# first.net
KiCad netlist of a schematic drawn in EAGLE
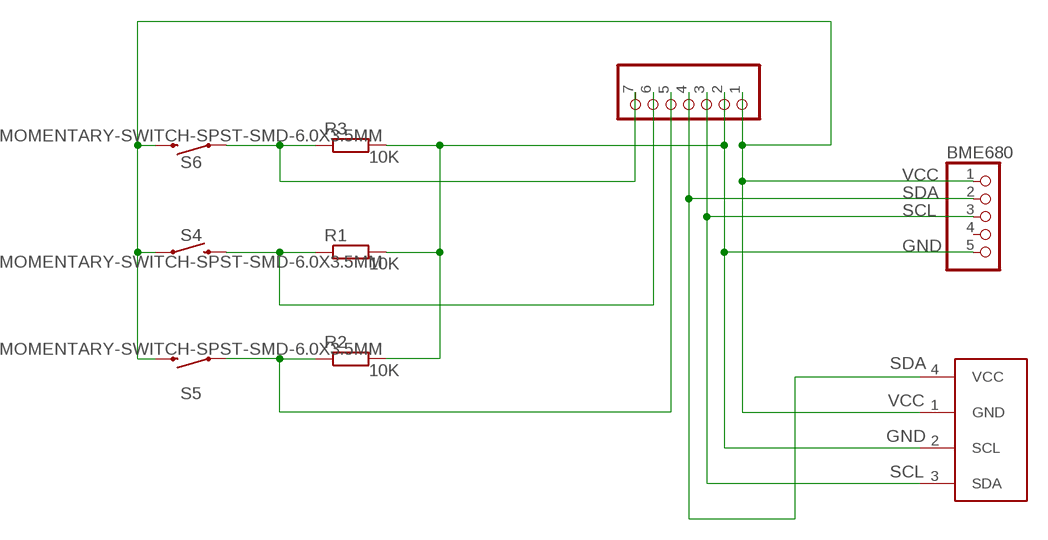
[diagram p0: schematic, sheet 1]

(export (version "E")
  (design (tool "Eeschema 10.0.6"))
  (components
    (comp (ref "BME680")
      (value "PINHD-1X5")
      (footprint "eagle-import:1X05")
      (libsource (lib "eagle-import") (part "PINHD-1X5"))
    )
    (comp (ref "R1")
      (value "R-EU_M1206")
      (footprint "eagle-import:M1206")
      (fields (field (name "SPICEPREFIX") "R") (field (name "SPICEPREFIX_1") "10K"))
      (libsource (lib "eagle-import") (part "R-EU_M1206"))
    )
    (comp (ref "R2")
      (value "R-EU_M1206")
      (footprint "eagle-import:M1206")
      (fields (field (name "SPICEPREFIX") "R") (field (name "SPICEPREFIX_1") "10K"))
      (libsource (lib "eagle-import") (part "R-EU_M1206"))
    )
    (comp (ref "R3")
      (value "R-EU_M1206")
      (footprint "eagle-import:M1206")
      (fields (field (name "SPICEPREFIX") "R") (field (name "SPICEPREFIX_1") "10K"))
      (libsource (lib "eagle-import") (part "R-EU_M1206"))
    )
    (comp (ref "S4")
      (value "MOMENTARY-SWITCH-SPST-SMD-6.0X3.5MM")
      (footprint "eagle-import:TACTILE_SWITCH_SMD_6.0X3.5MM")
      (libsource (lib "eagle-import") (part "MOMENTARY-SWITCH-SPST-SMD-6.0X3.5MM"))
    )
    (comp (ref "S5")
      (value "MOMENTARY-SWITCH-SPST-SMD-6.0X3.5MM")
      (footprint "eagle-import:TACTILE_SWITCH_SMD_6.0X3.5MM")
      (libsource (lib "eagle-import") (part "MOMENTARY-SWITCH-SPST-SMD-6.0X3.5MM"))
    )
    (comp (ref "S6")
      (value "MOMENTARY-SWITCH-SPST-SMD-6.0X3.5MM")
      (footprint "eagle-import:TACTILE_SWITCH_SMD_6.0X3.5MM")
      (libsource (lib "eagle-import") (part "MOMENTARY-SWITCH-SPST-SMD-6.0X3.5MM"))
    )
    (comp (ref "SDA")
      (value "PINHD-1X7")
      (footprint "eagle-import:1X07")
      (libsource (lib "eagle-import") (part "PINHD-1X7"))
    )
    (comp (ref "U$1")
      (value "I2C_OLED")
      (footprint "eagle-import:I2C_OLED_PACKAGE")
      (libsource (lib "eagle-import") (part "I2C_OLED"))
    )
  )
  (nets
    (net (code "1") (name "Net-(R1-Pad1)") (class "Default")
      (node (ref "R1") (pin "1") (pinfunction "1_1") (pintype "passive"))
      (node (ref "S4") (pin "2") (pinfunction "2_2") (pintype "passive"))
      (node (ref "SDA") (pin "6") (pinfunction "6_6") (pintype "passive"))
    )
    (net (code "2") (name "Net-(R2-Pad1)") (class "Default")
      (node (ref "R2") (pin "1") (pinfunction "1_1") (pintype "passive"))
      (node (ref "S5") (pin "1") (pinfunction "1_1") (pintype "passive"))
      (node (ref "SDA") (pin "5") (pinfunction "5_5") (pintype "passive"))
    )
    (net (code "3") (name "Net-(R3-Pad1)") (class "Default")
      (node (ref "R3") (pin "1") (pinfunction "1_1") (pintype "passive"))
      (node (ref "S6") (pin "1") (pinfunction "1_1") (pintype "passive"))
      (node (ref "SDA") (pin "7") (pinfunction "7_7") (pintype "passive"))
    )
    (net (code "4") (name "Net-(U$1-GND)") (class "Default")
      (node (ref "BME680") (pin "1") (pinfunction "1_1") (pintype "passive"))
      (node (ref "S4") (pin "1") (pinfunction "1_1") (pintype "passive"))
      (node (ref "S5") (pin "2") (pinfunction "2_2") (pintype "passive"))
      (node (ref "S6") (pin "2") (pinfunction "2_2") (pintype "passive"))
      (node (ref "SDA") (pin "1") (pinfunction "1_1") (pintype "passive"))
      (node (ref "U$1") (pin "1") (pinfunction "GND_1") (pintype "bidirectional"))
    )
    (net (code "5") (name "Net-(U$1-SCL)") (class "Default")
      (node (ref "BME680") (pin "5") (pinfunction "5_5") (pintype "passive"))
      (node (ref "R1") (pin "2") (pinfunction "2_2") (pintype "passive"))
      (node (ref "R2") (pin "2") (pinfunction "2_2") (pintype "passive"))
      (node (ref "R3") (pin "2") (pinfunction "2_2") (pintype "passive"))
      (node (ref "SDA") (pin "2") (pinfunction "2_2") (pintype "passive"))
      (node (ref "U$1") (pin "2") (pinfunction "SCL_2") (pintype "bidirectional"))
    )
    (net (code "6") (name "Net-(U$1-SDA)") (class "Default")
      (node (ref "BME680") (pin "3") (pinfunction "3_3") (pintype "passive"))
      (node (ref "SDA") (pin "3") (pinfunction "3_3") (pintype "passive"))
      (node (ref "U$1") (pin "3") (pinfunction "SDA_3") (pintype "bidirectional"))
    )
    (net (code "7") (name "Net-(U$1-VCC)") (class "Default")
      (node (ref "BME680") (pin "2") (pinfunction "2_2") (pintype "passive"))
      (node (ref "SDA") (pin "4") (pinfunction "4_4") (pintype "passive"))
      (node (ref "U$1") (pin "4") (pinfunction "VCC_4") (pintype "bidirectional"))
    )
    (net (code "8") (name "unconnected-(BME680-Pad4)") (class "Default")
      (node (ref "BME680") (pin "4") (pinfunction "4_4") (pintype "passive"))
    )
  )
)
